# PlacaBase12V.net
KiCad netlist of a schematic drawn in EAGLE
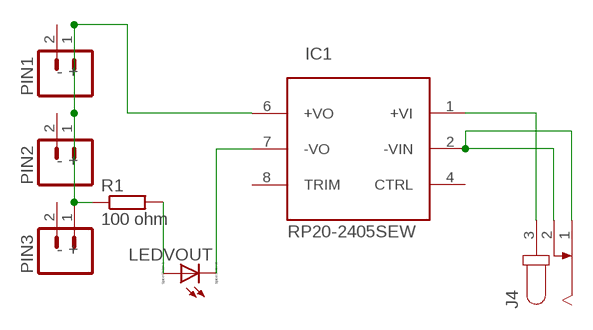
[diagram p0: schematic, sheet 1]

(export (version "E")
  (design (tool "Eeschema 10.0.6"))
  (components
    (comp (ref "IC1")
      (value "RP20-2405SEW")
      (footprint "eagle-import:PACKAGE_RP20-2405SEW")
      (libsource (lib "eagle-import") (part "RP20-2405SEW"))
    )
    (comp (ref "J4")
      (value "JACK-PLUG1")
      (footprint "eagle-import:SPC4078")
      (libsource (lib "eagle-import") (part "JACK-PLUG1"))
    )
    (comp (ref "LEDVOUT")
      (value "LED_ELD260")
      (footprint "eagle-import:LED_LD260")
      (libsource (lib "eagle-import") (part "LED_ELD260"))
    )
    (comp (ref "PIN1")
      (value "M02PTH4")
      (footprint "eagle-import:1X02_XTRA_BIG")
      (libsource (lib "eagle-import") (part "M02PTH4"))
    )
    (comp (ref "PIN2")
      (value "M02PTH4")
      (footprint "eagle-import:1X02_XTRA_BIG")
      (libsource (lib "eagle-import") (part "M02PTH4"))
    )
    (comp (ref "PIN3")
      (value "M02PTH4")
      (footprint "eagle-import:1X02_XTRA_BIG")
      (libsource (lib "eagle-import") (part "M02PTH4"))
    )
    (comp (ref "R1")
      (value "100 ohm")
      (footprint "eagle-import:0207_5V")
      (libsource (lib "eagle-import") (part "R-EU_0207/5V"))
    )
  )
  (nets
    (net (code "1") (name "Net-(IC1-+VI)") (class "Default")
      (node (ref "IC1") (pin "1") (pinfunction "+VI_1") (pintype "input"))
      (node (ref "J4") (pin "3") (pinfunction "3_3") (pintype "passive"))
    )
    (net (code "2") (name "Net-(IC1-+VO)") (class "Default")
      (node (ref "IC1") (pin "6") (pinfunction "+VO_6") (pintype "output"))
      (node (ref "PIN1") (pin "1") (pinfunction "1_1") (pintype "passive"))
      (node (ref "PIN2") (pin "1") (pinfunction "1_1") (pintype "passive"))
      (node (ref "PIN3") (pin "1") (pinfunction "1_1") (pintype "passive"))
      (node (ref "R1") (pin "1") (pinfunction "1_1") (pintype "passive"))
    )
    (net (code "3") (name "Net-(IC1--VIN)") (class "Default")
      (node (ref "IC1") (pin "2") (pinfunction "-VIN_2") (pintype "input"))
      (node (ref "J4") (pin "1") (pinfunction "1_1") (pintype "passive"))
      (node (ref "J4") (pin "2") (pinfunction "2_2") (pintype "passive"))
    )
    (net (code "4") (name "Net-(IC1--VO)") (class "Default")
      (node (ref "IC1") (pin "7") (pinfunction "-VO_7") (pintype "output"))
      (node (ref "LEDVOUT") (pin "K") (pinfunction "C_K") (pintype "passive"))
    )
    (net (code "5") (name "Net-(LEDVOUT-PadA)") (class "Default")
      (node (ref "LEDVOUT") (pin "A") (pinfunction "A_A") (pintype "passive"))
      (node (ref "R1") (pin "2") (pinfunction "2_2") (pintype "passive"))
    )
    (net (code "6") (name "unconnected-(IC1-CTRL-Pad4)") (class "Default")
      (node (ref "IC1") (pin "4") (pinfunction "CTRL_4") (pintype "bidirectional"))
    )
    (net (code "7") (name "unconnected-(IC1-TRIM-Pad8)") (class "Default")
      (node (ref "IC1") (pin "8") (pinfunction "TRIM_8") (pintype "bidirectional"))
    )
    (net (code "8") (name "unconnected-(PIN1-Pad2)") (class "Default")
      (node (ref "PIN1") (pin "2") (pinfunction "2_2") (pintype "passive"))
    )
    (net (code "9") (name "unconnected-(PIN2-Pad2)") (class "Default")
      (node (ref "PIN2") (pin "2") (pinfunction "2_2") (pintype "passive"))
    )
    (net (code "10") (name "unconnected-(PIN3-Pad2)") (class "Default")
      (node (ref "PIN3") (pin "2") (pinfunction "2_2") (pintype "passive"))
    )
  )
)
